# Indicators_and_Control.net
KiCad netlist of a schematic drawn in Altium Designer
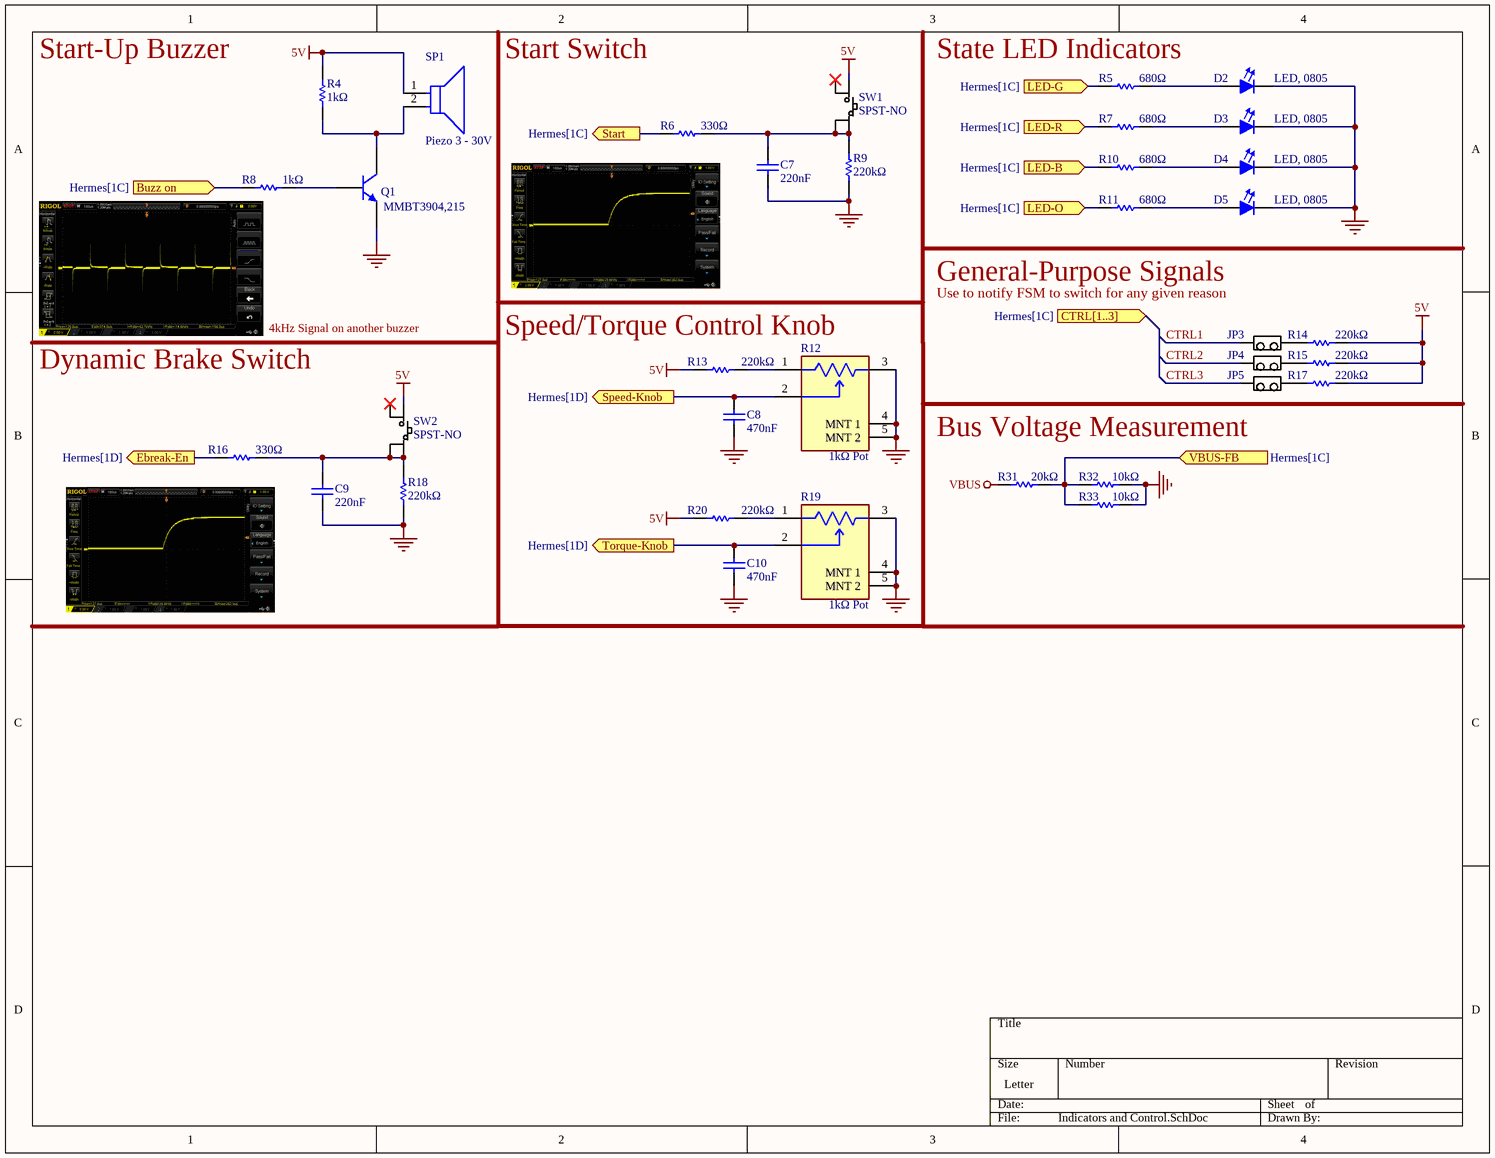
[diagram p0: Indicators and Control.SchDoc]

(export (version "E")
  (design (tool "Eeschema 10.0.6"))
  (components
    (comp (ref "C7")
      (value "220nF")
      (footprint "Footprints:CAP, 0603")
      (libsource (lib "499lib") (part "Cap, 0603"))
    )
    (comp (ref "C8")
      (value "470nF")
      (footprint "Footprints:CAP, 0603")
      (libsource (lib "499lib") (part "Cap, 0603"))
    )
    (comp (ref "C9")
      (value "220nF")
      (footprint "Footprints:CAP, 0603")
      (libsource (lib "499lib") (part "Cap, 0603"))
    )
    (comp (ref "C10")
      (value "470nF")
      (footprint "Footprints:CAP, 0603")
      (libsource (lib "499lib") (part "Cap, 0603"))
    )
    (comp (ref "D2")
      (value "LED, 0805")
      (footprint "Footprints:LED, 0805")
      (libsource (lib "499lib") (part "LED, 0805"))
    )
    (comp (ref "D3")
      (value "LED, 0805")
      (footprint "Footprints:LED, 0805")
      (libsource (lib "499lib") (part "LED, 0805"))
    )
    (comp (ref "D4")
      (value "LED, 0805")
      (footprint "Footprints:LED, 0805")
      (libsource (lib "499lib") (part "LED, 0805"))
    )
    (comp (ref "D5")
      (value "LED, 0805")
      (footprint "Footprints:LED, 0805")
      (libsource (lib "499lib") (part "LED, 0805"))
    )
    (comp (ref "JP3")
      (value "0.1\" Pitch")
      (footprint "Footprints:1x2, Header")
      (libsource (lib "499lib") (part "1x2 Pins"))
    )
    (comp (ref "JP4")
      (value "0.1\" Pitch")
      (footprint "Footprints:1x2, Header")
      (libsource (lib "499lib") (part "1x2 Pins"))
    )
    (comp (ref "JP5")
      (value "0.1\" Pitch")
      (footprint "Footprints:1x2, Header")
      (libsource (lib "499lib") (part "1x2 Pins"))
    )
    (comp (ref "Q1")
      (value "MMBT3904,215")
      (footprint "SOT-23")
      (description "NPN, 40V/200mA, 250mW, SOT-23")
      (fields
        (field (name "PUBLISHER") "Andy Bates")
        (field (name "SOURCE") "AUVic_Schematic_Library_Transistors.SchLib")
      )
      (libsource (lib "AUVIC") (part "Symbol"))
    )
    (comp (ref "R4")
      (value "1kΩ")
      (footprint "Footprints:Res, 0603")
      (libsource (lib "499lib") (part "Res, 0603"))
    )
    (comp (ref "R5")
      (value "680Ω")
      (footprint "Footprints:Res, 0603")
      (libsource (lib "499lib") (part "Res, 0603"))
    )
    (comp (ref "R6")
      (value "330Ω")
      (footprint "Footprints:Res, 0603")
      (libsource (lib "499lib") (part "Res, 0603"))
    )
    (comp (ref "R7")
      (value "680Ω")
      (footprint "Footprints:Res, 0603")
      (libsource (lib "499lib") (part "Res, 0603"))
    )
    (comp (ref "R8")
      (value "1kΩ")
      (footprint "Footprints:Res, 0603")
      (libsource (lib "499lib") (part "Res, 0603"))
    )
    (comp (ref "R9")
      (value "220kΩ")
      (footprint "Footprints:Res, 0603")
      (libsource (lib "499lib") (part "Res, 0603"))
    )
    (comp (ref "R10")
      (value "680Ω")
      (footprint "Footprints:Res, 0603")
      (libsource (lib "499lib") (part "Res, 0603"))
    )
    (comp (ref "R11")
      (value "680Ω")
      (footprint "Footprints:Res, 0603")
      (libsource (lib "499lib") (part "Res, 0603"))
    )
    (comp (ref "R12")
      (value "1kΩ Pot")
      (footprint "Footprints:1k Pot")
      (libsource (lib "499lib") (part "1kΩ Pot"))
    )
    (comp (ref "R13")
      (value "220kΩ")
      (footprint "Footprints:Res, 0603")
      (libsource (lib "499lib") (part "Res, 0603"))
    )
    (comp (ref "R14")
      (value "220kΩ")
      (footprint "Footprints:Res, 0603")
      (libsource (lib "499lib") (part "Res, 0603"))
    )
    (comp (ref "R15")
      (value "220kΩ")
      (footprint "Footprints:Res, 0603")
      (libsource (lib "499lib") (part "Res, 0603"))
    )
    (comp (ref "R16")
      (value "330Ω")
      (footprint "Footprints:Res, 0603")
      (libsource (lib "499lib") (part "Res, 0603"))
    )
    (comp (ref "R17")
      (value "220kΩ")
      (footprint "Footprints:Res, 0603")
      (libsource (lib "499lib") (part "Res, 0603"))
    )
    (comp (ref "R18")
      (value "220kΩ")
      (footprint "Footprints:Res, 0603")
      (libsource (lib "499lib") (part "Res, 0603"))
    )
    (comp (ref "R19")
      (value "1kΩ Pot")
      (footprint "Footprints:1k Pot")
      (libsource (lib "499lib") (part "1kΩ Pot"))
    )
    (comp (ref "R20")
      (value "220kΩ")
      (footprint "Footprints:Res, 0603")
      (libsource (lib "499lib") (part "Res, 0603"))
    )
    (comp (ref "R31")
      (value "20kΩ")
      (footprint "Footprints:Res, 0603")
      (libsource (lib "499lib") (part "Res, 0603"))
    )
    (comp (ref "R32")
      (value "10kΩ")
      (footprint "Footprints:Res, 0603")
      (libsource (lib "499lib") (part "Res, 0603"))
    )
    (comp (ref "R33")
      (value "10kΩ")
      (footprint "Footprints:Res, 0603")
      (libsource (lib "499lib") (part "Res, 0603"))
    )
    (comp (ref "SP1")
      (value "Piezo 3 - 30V")
      (footprint "FP-PKM13EPYH4000-A0-MFG")
      (description "Audio Buzzer Piezo 30Vo-p 3Vo-p 70dBA Through Hole Pin Ammo")
      (fields (field (name "MANUFACTURER") "TDK") (field (name "MANUFACTURER PART NUMBER") "PS1240P02BT"))
      (libsource (lib "499lib") (part "PS1240P02BT"))
    )
    (comp (ref "SW1")
      (value "SPST-NO")
      (footprint "Footprints:4-SPST-NO")
      (description "SPST-NO Switch")
      (libsource (lib "499lib") (part "Switch"))
    )
    (comp (ref "SW2")
      (value "SPST-NO")
      (footprint "Footprints:4-SPST-NO")
      (description "SPST-NO Switch")
      (libsource (lib "499lib") (part "Switch"))
    )
  )
  (nets
    (net (code "1") (name "/Buzz on") (class "Default")
      (node (ref "R8") (pin "1") (pinfunction "1_1") (pintype "passive"))
    )
    (net (code "2") (name "/CTRL1") (class "Default")
      (node (ref "JP3") (pin "2") (pinfunction "2_2") (pintype "passive"))
    )
    (net (code "3") (name "/CTRL2") (class "Default")
      (node (ref "JP4") (pin "2") (pinfunction "2_2") (pintype "passive"))
    )
    (net (code "4") (name "/CTRL3") (class "Default")
      (node (ref "JP5") (pin "2") (pinfunction "2_2") (pintype "passive"))
    )
    (net (code "6") (name "/Ebreak-En") (class "Default")
      (node (ref "R16") (pin "2") (pinfunction "2_2") (pintype "passive"))
    )
    (net (code "7") (name "/LED-B") (class "Default")
      (node (ref "R10") (pin "2") (pinfunction "2_2") (pintype "passive"))
    )
    (net (code "8") (name "/LED-G") (class "Default")
      (node (ref "R5") (pin "2") (pinfunction "2_2") (pintype "passive"))
    )
    (net (code "9") (name "/LED-O") (class "Default")
      (node (ref "R11") (pin "2") (pinfunction "2_2") (pintype "passive"))
    )
    (net (code "10") (name "/LED-R") (class "Default")
      (node (ref "R7") (pin "2") (pinfunction "2_2") (pintype "passive"))
    )
    (net (code "11") (name "/Speed-Knob") (class "Default")
      (node (ref "C8") (pin "1") (pinfunction "Anode_1") (pintype "passive"))
      (node (ref "R12") (pin "2") (pinfunction "2_2") (pintype "passive"))
    )
    (net (code "12") (name "/Start") (class "Default")
      (node (ref "R6") (pin "2") (pinfunction "2_2") (pintype "passive"))
    )
    (net (code "13") (name "/Torque-Knob") (class "Default")
      (node (ref "C10") (pin "1") (pinfunction "Anode_1") (pintype "passive"))
      (node (ref "R19") (pin "2") (pinfunction "2_2") (pintype "passive"))
    )
    (net (code "14") (name "/VBUS-FB") (class "Default")
      (node (ref "R31") (pin "1") (pinfunction "1_1") (pintype "passive"))
      (node (ref "R32") (pin "2") (pinfunction "2_2") (pintype "passive"))
      (node (ref "R33") (pin "2") (pinfunction "2_2") (pintype "passive"))
    )
    (net (code "15") (name "5V") (class "Default")
      (node (ref "R13") (pin "1") (pinfunction "1_1") (pintype "passive"))
      (node (ref "R14") (pin "1") (pinfunction "1_1") (pintype "passive"))
      (node (ref "R15") (pin "1") (pinfunction "1_1") (pintype "passive"))
      (node (ref "R17") (pin "1") (pinfunction "1_1") (pintype "passive"))
      (node (ref "R20") (pin "1") (pinfunction "1_1") (pintype "passive"))
      (node (ref "R4") (pin "1") (pinfunction "1_1") (pintype "passive"))
      (node (ref "SP1") (pin "1") (pinfunction "1_1") (pintype "passive"))
      (node (ref "SW1") (pin "4") (pinfunction "4_4") (pintype "passive"))
      (node (ref "SW2") (pin "4") (pinfunction "4_4") (pintype "passive"))
    )
    (net (code "16") (name "GND") (class "Default")
      (node (ref "C10") (pin "2") (pinfunction "Cathode_2") (pintype "passive"))
      (node (ref "C7") (pin "2") (pinfunction "Cathode_2") (pintype "passive"))
      (node (ref "C8") (pin "2") (pinfunction "Cathode_2") (pintype "passive"))
      (node (ref "C9") (pin "2") (pinfunction "Cathode_2") (pintype "passive"))
      (node (ref "D2") (pin "1") (pinfunction "Cathode_1") (pintype "passive"))
      (node (ref "D3") (pin "1") (pinfunction "Cathode_1") (pintype "passive"))
      (node (ref "D4") (pin "1") (pinfunction "Cathode_1") (pintype "passive"))
      (node (ref "D5") (pin "1") (pinfunction "Cathode_1") (pintype "passive"))
      (node (ref "Q1") (pin "2") (pinfunction "E_2") (pintype "passive"))
      (node (ref "R12") (pin "3") (pinfunction "3_3") (pintype "passive"))
      (node (ref "R12") (pin "4") (pinfunction "MNT_1_4") (pintype "passive"))
      (node (ref "R12") (pin "5") (pinfunction "MNT_2_5") (pintype "passive"))
      (node (ref "R18") (pin "1") (pinfunction "1_1") (pintype "passive"))
      (node (ref "R19") (pin "3") (pinfunction "3_3") (pintype "passive"))
      (node (ref "R19") (pin "4") (pinfunction "MNT_1_4") (pintype "passive"))
      (node (ref "R19") (pin "5") (pinfunction "MNT_2_5") (pintype "passive"))
      (node (ref "R32") (pin "1") (pinfunction "1_1") (pintype "passive"))
      (node (ref "R33") (pin "1") (pinfunction "1_1") (pintype "passive"))
      (node (ref "R9") (pin "1") (pinfunction "1_1") (pintype "passive"))
    )
    (net (code "17") (name "Net-(C7-Anode)") (class "Default")
      (node (ref "C7") (pin "1") (pinfunction "Anode_1") (pintype "passive"))
      (node (ref "R6") (pin "1") (pinfunction "1_1") (pintype "passive"))
      (node (ref "R9") (pin "2") (pinfunction "2_2") (pintype "passive"))
      (node (ref "SW1") (pin "1") (pinfunction "1_1") (pintype "passive"))
      (node (ref "SW1") (pin "2") (pinfunction "2_2") (pintype "passive"))
    )
    (net (code "18") (name "Net-(C9-Anode)") (class "Default")
      (node (ref "C9") (pin "1") (pinfunction "Anode_1") (pintype "passive"))
      (node (ref "R16") (pin "1") (pinfunction "1_1") (pintype "passive"))
      (node (ref "R18") (pin "2") (pinfunction "2_2") (pintype "passive"))
      (node (ref "SW2") (pin "1") (pinfunction "1_1") (pintype "passive"))
      (node (ref "SW2") (pin "2") (pinfunction "2_2") (pintype "passive"))
    )
    (net (code "19") (name "Net-(D2-Anode)") (class "Default")
      (node (ref "D2") (pin "2") (pinfunction "Anode_2") (pintype "passive"))
      (node (ref "R5") (pin "1") (pinfunction "1_1") (pintype "passive"))
    )
    (net (code "20") (name "Net-(D3-Anode)") (class "Default")
      (node (ref "D3") (pin "2") (pinfunction "Anode_2") (pintype "passive"))
      (node (ref "R7") (pin "1") (pinfunction "1_1") (pintype "passive"))
    )
    (net (code "21") (name "Net-(D4-Anode)") (class "Default")
      (node (ref "D4") (pin "2") (pinfunction "Anode_2") (pintype "passive"))
      (node (ref "R10") (pin "1") (pinfunction "1_1") (pintype "passive"))
    )
    (net (code "22") (name "Net-(D5-Anode)") (class "Default")
      (node (ref "D5") (pin "2") (pinfunction "Anode_2") (pintype "passive"))
      (node (ref "R11") (pin "1") (pinfunction "1_1") (pintype "passive"))
    )
    (net (code "23") (name "Net-(JP3-Pad1)") (class "Default")
      (node (ref "JP3") (pin "1") (pinfunction "1_1") (pintype "passive"))
      (node (ref "R14") (pin "2") (pinfunction "2_2") (pintype "passive"))
    )
    (net (code "24") (name "Net-(JP4-Pad1)") (class "Default")
      (node (ref "JP4") (pin "1") (pinfunction "1_1") (pintype "passive"))
      (node (ref "R15") (pin "2") (pinfunction "2_2") (pintype "passive"))
    )
    (net (code "25") (name "Net-(JP5-Pad1)") (class "Default")
      (node (ref "JP5") (pin "1") (pinfunction "1_1") (pintype "passive"))
      (node (ref "R17") (pin "2") (pinfunction "2_2") (pintype "passive"))
    )
    (net (code "26") (name "Net-(Q1-B)") (class "Default")
      (node (ref "Q1") (pin "1") (pinfunction "B_1") (pintype "passive"))
      (node (ref "R8") (pin "2") (pinfunction "2_2") (pintype "passive"))
    )
    (net (code "27") (name "Net-(Q1-C)") (class "Default")
      (node (ref "Q1") (pin "3") (pinfunction "C_3") (pintype "passive"))
      (node (ref "R4") (pin "2") (pinfunction "2_2") (pintype "passive"))
      (node (ref "SP1") (pin "2") (pinfunction "2_2") (pintype "passive"))
    )
    (net (code "28") (name "Net-(R12-Pad1)") (class "Default")
      (node (ref "R12") (pin "1") (pinfunction "1_1") (pintype "passive"))
      (node (ref "R13") (pin "2") (pinfunction "2_2") (pintype "passive"))
    )
    (net (code "29") (name "Net-(R19-Pad1)") (class "Default")
      (node (ref "R19") (pin "1") (pinfunction "1_1") (pintype "passive"))
      (node (ref "R20") (pin "2") (pinfunction "2_2") (pintype "passive"))
    )
    (net (code "30") (name "VBUS") (class "Default")
      (node (ref "R31") (pin "2") (pinfunction "2_2") (pintype "passive"))
    )
    (net (code "31") (name "unconnected-(SW1-Pad3)") (class "Default")
      (node (ref "SW1") (pin "3") (pinfunction "3_3") (pintype "passive+no_connect"))
    )
    (net (code "32") (name "unconnected-(SW2-Pad3)") (class "Default")
      (node (ref "SW2") (pin "3") (pinfunction "3_3") (pintype "passive+no_connect"))
    )
  )
)
